# DISPLAY.net
KiCad netlist of a schematic drawn in Altium Designer
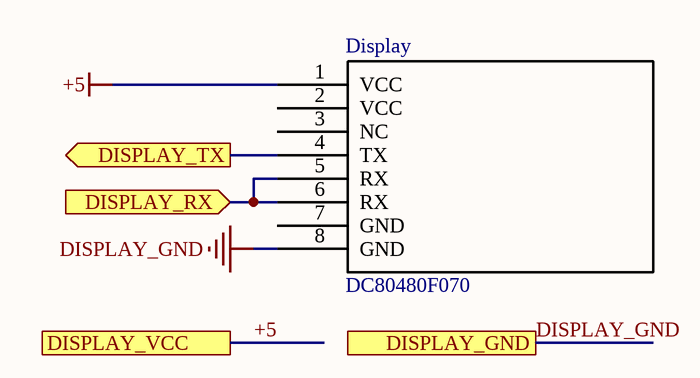
[diagram p0: DISPLAY.SchDoc]

(export (version "E")
  (design (tool "Eeschema 10.0.6"))
  (components (comp (ref "Display") (value "DC80480F070") (libsource (lib "Schlib1") (part "DC80480F070"))))
  (nets
    (net (code "1") (name "+5") (class "Default")
      (node (ref "Display") (pin "1") (pinfunction "VCC_1") (pintype "passive"))
    )
    (net (code "2") (name "/DISPLAY_RX") (class "Default")
      (node (ref "Display") (pin "5") (pinfunction "RX_5") (pintype "passive"))
      (node (ref "Display") (pin "6") (pinfunction "RX_6") (pintype "passive"))
    )
    (net (code "3") (name "/DISPLAY_TX") (class "Default")
      (node (ref "Display") (pin "4") (pinfunction "TX_4") (pintype "passive"))
    )
    (net (code "4") (name "DISPLAY_GND") (class "Default")
      (node (ref "Display") (pin "8") (pinfunction "GND_8") (pintype "passive"))
    )
    (net (code "5") (name "unconnected-(Display-GND-Pad7)") (class "Default")
      (node (ref "Display") (pin "7") (pinfunction "GND_7") (pintype "passive"))
    )
    (net (code "6") (name "unconnected-(Display-NC-Pad3)") (class "Default")
      (node (ref "Display") (pin "3") (pinfunction "NC_3") (pintype "passive"))
    )
    (net (code "7") (name "unconnected-(Display-VCC-Pad2)") (class "Default")
      (node (ref "Display") (pin "2") (pinfunction "VCC_2") (pintype "passive"))
    )
  )
)
